# MCU.net
KiCad netlist of a schematic drawn in Altium Designer
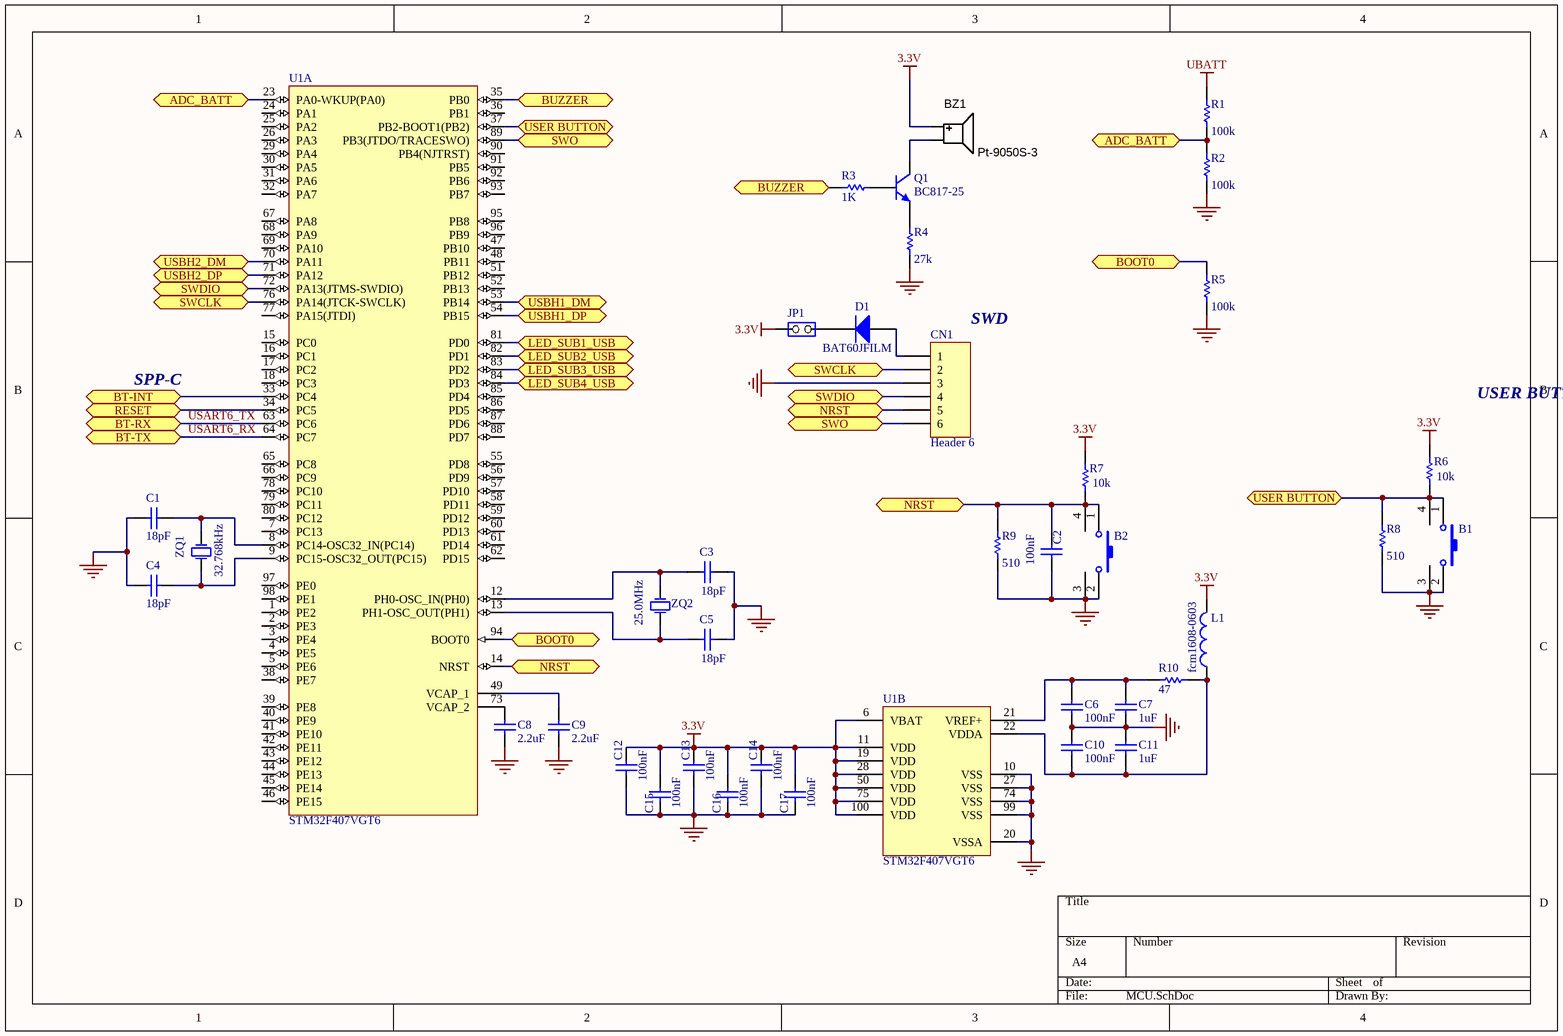
[diagram p0: MCU.SchDoc]

(export (version "E")
  (design (tool "Eeschema 10.0.6"))
  (components
    (comp (ref "B1")
      (value "SW-PB")
      (footprint "SPST-2")
      (description "Switch")
      (fields (field (name "PUBLISHER") "Altium Limited"))
      (libsource (lib "Miscellaneous Devices") (part "SW-PB"))
    )
    (comp (ref "B2")
      (value "SW-PB")
      (footprint "SPST-2")
      (description "Switch")
      (fields (field (name "PUBLISHER") "Altium Limited"))
      (libsource (lib "Miscellaneous Devices") (part "SW-PB"))
    )
    (comp (ref "BZ1")
      (value "Pt-9050S-3")
      (footprint "BUZZER_12.0X8.5MM")
      (description "Speaker, Magnetic Transducer")
      (libsource (lib "PBL - Electromechanical") (part "BZ_12x8.5x6.5_2kHz"))
    )
    (comp (ref "C1")
      (value "18pF")
      (footprint "RAD-0.3")
      (description "Capacitor")
      (fields (field (name "Comment") "Cap") (field (name "PUBLISHER") "Altium Limited"))
      (libsource (lib "Miscellaneous Devices") (part "Cap"))
    )
    (comp (ref "C2")
      (value "100nF")
      (footprint "RAD-0.3")
      (description "Capacitor")
      (fields (field (name "Comment") "Cap") (field (name "PUBLISHER") "Altium Limited"))
      (libsource (lib "Miscellaneous Devices") (part "Cap"))
    )
    (comp (ref "C3")
      (value "18pF")
      (footprint "RAD-0.3")
      (description "Capacitor")
      (fields (field (name "Comment") "Cap") (field (name "PUBLISHER") "Altium Limited"))
      (libsource (lib "Miscellaneous Devices") (part "Cap"))
    )
    (comp (ref "C4")
      (value "18pF")
      (footprint "RAD-0.3")
      (description "Capacitor")
      (fields (field (name "Comment") "Cap") (field (name "PUBLISHER") "Altium Limited"))
      (libsource (lib "Miscellaneous Devices") (part "Cap"))
    )
    (comp (ref "C5")
      (value "18pF")
      (footprint "RAD-0.3")
      (description "Capacitor")
      (fields (field (name "Comment") "Cap") (field (name "PUBLISHER") "Altium Limited"))
      (libsource (lib "Miscellaneous Devices") (part "Cap"))
    )
    (comp (ref "C6")
      (value "100nF")
      (footprint "RAD-0.3")
      (description "Capacitor")
      (fields (field (name "Comment") "Cap") (field (name "PUBLISHER") "Altium Limited"))
      (libsource (lib "Miscellaneous Devices") (part "Cap"))
    )
    (comp (ref "C7")
      (value "1uF")
      (footprint "RAD-0.3")
      (description "Capacitor")
      (fields (field (name "Comment") "Cap") (field (name "PUBLISHER") "Altium Limited"))
      (libsource (lib "Miscellaneous Devices") (part "Cap"))
    )
    (comp (ref "C8")
      (value "2.2uF")
      (footprint "RAD-0.3")
      (description "Capacitor")
      (fields (field (name "Comment") "Cap") (field (name "PUBLISHER") "Altium Limited"))
      (libsource (lib "Miscellaneous Devices") (part "Cap"))
    )
    (comp (ref "C9")
      (value "2.2uF")
      (footprint "RAD-0.3")
      (description "Capacitor")
      (fields (field (name "Comment") "Cap") (field (name "PUBLISHER") "Altium Limited"))
      (libsource (lib "Miscellaneous Devices") (part "Cap"))
    )
    (comp (ref "C10")
      (value "100nF")
      (footprint "RAD-0.3")
      (description "Capacitor")
      (fields (field (name "Comment") "Cap") (field (name "PUBLISHER") "Altium Limited"))
      (libsource (lib "Miscellaneous Devices") (part "Cap"))
    )
    (comp (ref "C11")
      (value "1uF")
      (footprint "RAD-0.3")
      (description "Capacitor")
      (fields (field (name "Comment") "Cap") (field (name "PUBLISHER") "Altium Limited"))
      (libsource (lib "Miscellaneous Devices") (part "Cap"))
    )
    (comp (ref "C12")
      (value "100nF")
      (footprint "RAD-0.3")
      (description "Capacitor")
      (fields (field (name "Comment") "Cap") (field (name "PUBLISHER") "Altium Limited"))
      (libsource (lib "Miscellaneous Devices") (part "Cap"))
    )
    (comp (ref "C13")
      (value "100nF")
      (footprint "RAD-0.3")
      (description "Capacitor")
      (fields (field (name "Comment") "Cap") (field (name "PUBLISHER") "Altium Limited"))
      (libsource (lib "Miscellaneous Devices") (part "Cap"))
    )
    (comp (ref "C14")
      (value "100nF")
      (footprint "RAD-0.3")
      (description "Capacitor")
      (fields (field (name "Comment") "Cap") (field (name "PUBLISHER") "Altium Limited"))
      (libsource (lib "Miscellaneous Devices") (part "Cap"))
    )
    (comp (ref "C15")
      (value "100nF")
      (footprint "RAD-0.3")
      (description "Capacitor")
      (fields (field (name "Comment") "Cap") (field (name "PUBLISHER") "Altium Limited"))
      (libsource (lib "Miscellaneous Devices") (part "Cap"))
    )
    (comp (ref "C16")
      (value "100nF")
      (footprint "RAD-0.3")
      (description "Capacitor")
      (fields (field (name "Comment") "Cap") (field (name "PUBLISHER") "Altium Limited"))
      (libsource (lib "Miscellaneous Devices") (part "Cap"))
    )
    (comp (ref "C17")
      (value "100nF")
      (footprint "RAD-0.3")
      (description "Capacitor")
      (fields (field (name "Comment") "Cap") (field (name "PUBLISHER") "Altium Limited"))
      (libsource (lib "Miscellaneous Devices") (part "Cap"))
    )
    (comp (ref "CN1")
      (value "Header 6")
      (footprint "HDR1X6")
      (description "Header, 6-Pin")
      (fields (field (name "PUBLISHER") "Altium Limited"))
      (libsource (lib "Miscellaneous Connectors") (part "Header 6"))
    )
    (comp (ref "D1")
      (value "BAT60JFILM")
      (footprint "SOD323/A")
      (fields (field (name "PUBLISHER") "Altium Limited"))
      (libsource (lib "MB997") (part "BAT60JFILM"))
    )
    (comp (ref "JP1") (value "~") (footprint "SIP2/2.54") (libsource (lib "*") (part "JP2")))
    (comp (ref "L1")
      (value "fcm1608-0603")
      (footprint "0402-A")
      (description "Inductor")
      (fields (field (name "PUBLISHER") "Altium Limited"))
      (libsource (lib "Miscellaneous Devices") (part "Inductor"))
    )
    (comp (ref "Q1")
      (value "BC817-25")
      (footprint "TO-226-AA")
      (description "NPN Bipolar Transistor")
      (fields (field (name "PUBLISHER") "Altium Limited"))
      (libsource (lib "Miscellaneous Devices") (part "NPN"))
    )
    (comp (ref "R1")
      (value "100k")
      (footprint "AXIAL-0.3")
      (description "Resistor")
      (fields (field (name "Comment") "Res1") (field (name "PUBLISHER") "Altium Limited"))
      (libsource (lib "Miscellaneous Devices") (part "Res1"))
    )
    (comp (ref "R2")
      (value "100k")
      (footprint "AXIAL-0.3")
      (description "Resistor")
      (fields (field (name "Comment") "Res1") (field (name "PUBLISHER") "Altium Limited"))
      (libsource (lib "Miscellaneous Devices") (part "Res1"))
    )
    (comp (ref "R3")
      (value "1K")
      (footprint "AXIAL-0.3")
      (description "Resistor")
      (fields (field (name "Comment") "Res1") (field (name "PUBLISHER") "Altium Limited"))
      (libsource (lib "Miscellaneous Devices") (part "Res1"))
    )
    (comp (ref "R4")
      (value "27k")
      (footprint "AXIAL-0.3")
      (description "Resistor")
      (fields (field (name "Comment") "Res1") (field (name "PUBLISHER") "Altium Limited"))
      (libsource (lib "Miscellaneous Devices") (part "Res1"))
    )
    (comp (ref "R5")
      (value "100k")
      (footprint "AXIAL-0.3")
      (description "Resistor")
      (fields (field (name "Comment") "Res1") (field (name "PUBLISHER") "Altium Limited"))
      (libsource (lib "Miscellaneous Devices") (part "Res1"))
    )
    (comp (ref "R6")
      (value "10k")
      (footprint "AXIAL-0.3")
      (description "Resistor")
      (fields (field (name "Comment") "Res1") (field (name "PUBLISHER") "Altium Limited"))
      (libsource (lib "Miscellaneous Devices") (part "Res1"))
    )
    (comp (ref "R7")
      (value "10k")
      (footprint "AXIAL-0.3")
      (description "Resistor")
      (fields (field (name "Comment") "Res1") (field (name "PUBLISHER") "Altium Limited"))
      (libsource (lib "Miscellaneous Devices") (part "Res1"))
    )
    (comp (ref "R8")
      (value "510")
      (footprint "AXIAL-0.3")
      (description "Resistor")
      (fields (field (name "Comment") "Res1") (field (name "PUBLISHER") "Altium Limited"))
      (libsource (lib "Miscellaneous Devices") (part "Res1"))
    )
    (comp (ref "R9")
      (value "510")
      (footprint "AXIAL-0.3")
      (description "Resistor")
      (fields (field (name "Comment") "Res1") (field (name "PUBLISHER") "Altium Limited"))
      (libsource (lib "Miscellaneous Devices") (part "Res1"))
    )
    (comp (ref "R10")
      (value "47")
      (footprint "AXIAL-0.3")
      (description "Resistor")
      (fields (field (name "Comment") "Res1") (field (name "PUBLISHER") "Altium Limited"))
      (libsource (lib "Miscellaneous Devices") (part "Res1"))
    )
    (comp (ref "U1")
      (value "STM32F407VGT6")
      (footprint "STM-LQFP100_N")
      (fields (field (name "MANUFACTURER") "STMicroelectronics"))
      (libsource (lib "") (part "STM32F407VGT6_1"))
    )
    (comp (ref "ZQ1")
      (value "32.768kHz")
      (footprint "R38")
      (description "Crystal Oscillator")
      (fields (field (name "Comment") "XTAL") (field (name "PUBLISHER") "Altium Limited"))
      (libsource (lib "Miscellaneous Devices") (part "XTAL"))
    )
    (comp (ref "ZQ2")
      (value "25.0MHz")
      (footprint "R38")
      (description "Crystal Oscillator")
      (fields (field (name "Comment") "XTAL") (field (name "PUBLISHER") "Altium Limited"))
      (libsource (lib "Miscellaneous Devices") (part "XTAL"))
    )
  )
  (nets
    (net (code "1") (name "/ADC_BATT") (class "Default")
      (node (ref "R1") (pin "1") (pinfunction "1_1") (pintype "passive"))
      (node (ref "R2") (pin "2") (pinfunction "2_2") (pintype "passive"))
      (node (ref "U1") (pin "23") (pinfunction "PA0-WKUP(PA0)_23") (pintype "bidirectional"))
    )
    (net (code "2") (name "/BOOT0") (class "Default")
      (node (ref "R5") (pin "2") (pinfunction "2_2") (pintype "passive"))
      (node (ref "U1") (pin "94") (pinfunction "BOOT0_94") (pintype "input"))
    )
    (net (code "3") (name "/BT-INT") (class "Default")
      (node (ref "U1") (pin "33") (pinfunction "PC4_33") (pintype "bidirectional"))
    )
    (net (code "4") (name "/BUZZER") (class "Default")
      (node (ref "R3") (pin "2") (pinfunction "2_2") (pintype "passive"))
      (node (ref "U1") (pin "35") (pinfunction "PB0_35") (pintype "bidirectional"))
    )
    (net (code "5") (name "/LED_SUB1_USB") (class "Default")
      (node (ref "U1") (pin "81") (pinfunction "PD0_81") (pintype "bidirectional"))
    )
    (net (code "6") (name "/LED_SUB2_USB") (class "Default")
      (node (ref "U1") (pin "82") (pinfunction "PD1_82") (pintype "bidirectional"))
    )
    (net (code "7") (name "/LED_SUB3_USB") (class "Default")
      (node (ref "U1") (pin "83") (pinfunction "PD2_83") (pintype "bidirectional"))
    )
    (net (code "8") (name "/LED_SUB4_USB") (class "Default")
      (node (ref "U1") (pin "84") (pinfunction "PD3_84") (pintype "bidirectional"))
    )
    (net (code "9") (name "/NRST") (class "Default")
      (node (ref "B2") (pin "1") (pinfunction "1_1") (pintype "passive"))
      (node (ref "B2") (pin "4") (pinfunction "4_4") (pintype "passive"))
      (node (ref "C2") (pin "2") (pinfunction "2_2") (pintype "passive"))
      (node (ref "CN1") (pin "5") (pinfunction "5_5") (pintype "passive"))
      (node (ref "R7") (pin "1") (pinfunction "1_1") (pintype "passive"))
      (node (ref "R9") (pin "2") (pinfunction "2_2") (pintype "passive"))
      (node (ref "U1") (pin "14") (pinfunction "NRST_14") (pintype "bidirectional"))
    )
    (net (code "10") (name "/RESET") (class "Default")
      (node (ref "U1") (pin "34") (pinfunction "PC5_34") (pintype "bidirectional"))
    )
    (net (code "11") (name "/SWCLK") (class "Default")
      (node (ref "CN1") (pin "2") (pinfunction "2_2") (pintype "passive"))
      (node (ref "U1") (pin "76") (pinfunction "PA14(JTCK-SWCLK)_76") (pintype "bidirectional"))
    )
    (net (code "12") (name "/SWDIO") (class "Default")
      (node (ref "CN1") (pin "4") (pinfunction "4_4") (pintype "passive"))
      (node (ref "U1") (pin "72") (pinfunction "PA13(JTMS-SWDIO)_72") (pintype "bidirectional"))
    )
    (net (code "13") (name "/SWO") (class "Default")
      (node (ref "CN1") (pin "6") (pinfunction "6_6") (pintype "passive"))
      (node (ref "U1") (pin "89") (pinfunction "PB3(JTDO/TRACESWO)_89") (pintype "bidirectional"))
    )
    (net (code "14") (name "/USART6_RX") (class "Default")
      (node (ref "U1") (pin "64") (pinfunction "PC7_64") (pintype "bidirectional"))
    )
    (net (code "15") (name "/USART6_TX") (class "Default")
      (node (ref "U1") (pin "63") (pinfunction "PC6_63") (pintype "bidirectional"))
    )
    (net (code "16") (name "/USBH1_DM") (class "Default")
      (node (ref "U1") (pin "53") (pinfunction "PB14_53") (pintype "bidirectional"))
    )
    (net (code "17") (name "/USBH1_DP") (class "Default")
      (node (ref "U1") (pin "54") (pinfunction "PB15_54") (pintype "bidirectional"))
    )
    (net (code "18") (name "/USBH2_DM") (class "Default")
      (node (ref "U1") (pin "70") (pinfunction "PA11_70") (pintype "bidirectional"))
    )
    (net (code "19") (name "/USBH2_DP") (class "Default")
      (node (ref "U1") (pin "71") (pinfunction "PA12_71") (pintype "bidirectional"))
    )
    (net (code "20") (name "/USER BUTTON") (class "Default")
      (node (ref "B1") (pin "1") (pinfunction "1_1") (pintype "passive"))
      (node (ref "B1") (pin "4") (pinfunction "4_4") (pintype "passive"))
      (node (ref "R6") (pin "1") (pinfunction "1_1") (pintype "passive"))
      (node (ref "R8") (pin "2") (pinfunction "2_2") (pintype "passive"))
      (node (ref "U1") (pin "37") (pinfunction "PB2-BOOT1(PB2)_37") (pintype "bidirectional"))
    )
    (net (code "21") (name "3.3V") (class "Default")
      (node (ref "BZ1") (pin "1") (pinfunction "Positive_1") (pintype "passive"))
      (node (ref "C12") (pin "1") (pinfunction "1_1") (pintype "passive"))
      (node (ref "C13") (pin "1") (pinfunction "1_1") (pintype "passive"))
      (node (ref "C14") (pin "1") (pinfunction "1_1") (pintype "passive"))
      (node (ref "C15") (pin "1") (pinfunction "1_1") (pintype "passive"))
      (node (ref "C16") (pin "1") (pinfunction "1_1") (pintype "passive"))
      (node (ref "C17") (pin "1") (pinfunction "1_1") (pintype "passive"))
      (node (ref "JP1") (pin "2") (pinfunction "NO_2") (pintype "passive"))
      (node (ref "L1") (pin "2") (pinfunction "2_2") (pintype "passive"))
      (node (ref "R6") (pin "2") (pinfunction "2_2") (pintype "passive"))
      (node (ref "R7") (pin "2") (pinfunction "2_2") (pintype "passive"))
      (node (ref "U1") (pin "100") (pinfunction "VDD_100") (pintype "power_in"))
      (node (ref "U1") (pin "11") (pinfunction "VDD_11") (pintype "power_in"))
      (node (ref "U1") (pin "19") (pinfunction "VDD_19") (pintype "power_in"))
      (node (ref "U1") (pin "28") (pinfunction "VDD_28") (pintype "power_in"))
      (node (ref "U1") (pin "50") (pinfunction "VDD_50") (pintype "power_in"))
      (node (ref "U1") (pin "6") (pinfunction "VBAT_6") (pintype "power_in"))
      (node (ref "U1") (pin "75") (pinfunction "VDD_75") (pintype "power_in"))
    )
    (net (code "22") (name "GND") (class "Default")
      (node (ref "B1") (pin "2") (pinfunction "2_2") (pintype "passive"))
      (node (ref "B1") (pin "3") (pinfunction "3_3") (pintype "passive"))
      (node (ref "B2") (pin "2") (pinfunction "2_2") (pintype "passive"))
      (node (ref "B2") (pin "3") (pinfunction "3_3") (pintype "passive"))
      (node (ref "C1") (pin "2") (pinfunction "2_2") (pintype "passive"))
      (node (ref "C10") (pin "2") (pinfunction "2_2") (pintype "passive"))
      (node (ref "C11") (pin "2") (pinfunction "2_2") (pintype "passive"))
      (node (ref "C12") (pin "2") (pinfunction "2_2") (pintype "passive"))
      (node (ref "C13") (pin "2") (pinfunction "2_2") (pintype "passive"))
      (node (ref "C14") (pin "2") (pinfunction "2_2") (pintype "passive"))
      (node (ref "C15") (pin "2") (pinfunction "2_2") (pintype "passive"))
      (node (ref "C16") (pin "2") (pinfunction "2_2") (pintype "passive"))
      (node (ref "C17") (pin "2") (pinfunction "2_2") (pintype "passive"))
      (node (ref "C2") (pin "1") (pinfunction "1_1") (pintype "passive"))
      (node (ref "C3") (pin "2") (pinfunction "2_2") (pintype "passive"))
      (node (ref "C4") (pin "2") (pinfunction "2_2") (pintype "passive"))
      (node (ref "C5") (pin "2") (pinfunction "2_2") (pintype "passive"))
      (node (ref "C6") (pin "1") (pinfunction "1_1") (pintype "passive"))
      (node (ref "C7") (pin "1") (pinfunction "1_1") (pintype "passive"))
      (node (ref "C8") (pin "2") (pinfunction "2_2") (pintype "passive"))
      (node (ref "C9") (pin "2") (pinfunction "2_2") (pintype "passive"))
      (node (ref "CN1") (pin "3") (pinfunction "3_3") (pintype "passive"))
      (node (ref "R2") (pin "1") (pinfunction "1_1") (pintype "passive"))
      (node (ref "R4") (pin "1") (pinfunction "1_1") (pintype "passive"))
      (node (ref "R5") (pin "1") (pinfunction "1_1") (pintype "passive"))
      (node (ref "R8") (pin "1") (pinfunction "1_1") (pintype "passive"))
      (node (ref "R9") (pin "1") (pinfunction "1_1") (pintype "passive"))
      (node (ref "U1") (pin "10") (pinfunction "VSS_10") (pintype "power_in"))
      (node (ref "U1") (pin "20") (pinfunction "VSSA_20") (pintype "power_in"))
      (node (ref "U1") (pin "27") (pinfunction "VSS_27") (pintype "power_in"))
      (node (ref "U1") (pin "74") (pinfunction "VSS_74") (pintype "power_in"))
      (node (ref "U1") (pin "99") (pinfunction "VSS_99") (pintype "power_in"))
    )
    (net (code "23") (name "Net-(BZ1-Negative)") (class "Default")
      (node (ref "BZ1") (pin "2") (pinfunction "Negative_2") (pintype "passive"))
      (node (ref "Q1") (pin "1") (pinfunction "C_1") (pintype "passive"))
    )
    (net (code "24") (name "Net-(D1-A)") (class "Default")
      (node (ref "CN1") (pin "1") (pinfunction "1_1") (pintype "passive"))
      (node (ref "D1") (pin "1") (pinfunction "A_1") (pintype "passive"))
    )
    (net (code "25") (name "Net-(D1-K)") (class "Default")
      (node (ref "D1") (pin "2") (pinfunction "K_2") (pintype "passive"))
      (node (ref "JP1") (pin "1") (pinfunction "COMMON_1") (pintype "passive"))
    )
    (net (code "26") (name "Net-(Q1-B)") (class "Default")
      (node (ref "Q1") (pin "2") (pinfunction "B_2") (pintype "passive"))
      (node (ref "R3") (pin "1") (pinfunction "1_1") (pintype "passive"))
    )
    (net (code "27") (name "Net-(Q1-E)") (class "Default")
      (node (ref "Q1") (pin "3") (pinfunction "E_3") (pintype "passive"))
      (node (ref "R4") (pin "2") (pinfunction "2_2") (pintype "passive"))
    )
    (net (code "28") (name "Net-(U1A-PC14-OSC32_IN(PC14))") (class "Default")
      (node (ref "C1") (pin "1") (pinfunction "1_1") (pintype "passive"))
      (node (ref "U1") (pin "8") (pinfunction "PC14-OSC32_IN(PC14)_8") (pintype "bidirectional"))
      (node (ref "ZQ1") (pin "2") (pinfunction "OSC2_2") (pintype "passive"))
    )
    (net (code "29") (name "Net-(U1A-PC15-OSC32_OUT(PC15))") (class "Default")
      (node (ref "C4") (pin "1") (pinfunction "1_1") (pintype "passive"))
      (node (ref "U1") (pin "9") (pinfunction "PC15-OSC32_OUT(PC15)_9") (pintype "bidirectional"))
      (node (ref "ZQ1") (pin "1") (pinfunction "OSC1_1") (pintype "passive"))
    )
    (net (code "30") (name "Net-(U1A-PH0-OSC_IN(PH0))") (class "Default")
      (node (ref "C3") (pin "1") (pinfunction "1_1") (pintype "passive"))
      (node (ref "U1") (pin "12") (pinfunction "PH0-OSC_IN(PH0)_12") (pintype "bidirectional"))
      (node (ref "ZQ2") (pin "1") (pinfunction "OSC1_1") (pintype "passive"))
    )
    (net (code "31") (name "Net-(U1A-PH1-OSC_OUT(PH1))") (class "Default")
      (node (ref "C5") (pin "1") (pinfunction "1_1") (pintype "passive"))
      (node (ref "U1") (pin "13") (pinfunction "PH1-OSC_OUT(PH1)_13") (pintype "bidirectional"))
      (node (ref "ZQ2") (pin "2") (pinfunction "OSC2_2") (pintype "passive"))
    )
    (net (code "32") (name "Net-(U1A-VCAP_1)") (class "Default")
      (node (ref "C9") (pin "1") (pinfunction "1_1") (pintype "passive"))
      (node (ref "U1") (pin "49") (pinfunction "VCAP_1_49") (pintype "power_in"))
    )
    (net (code "33") (name "Net-(U1A-VCAP_2)") (class "Default")
      (node (ref "C8") (pin "1") (pinfunction "1_1") (pintype "passive"))
      (node (ref "U1") (pin "73") (pinfunction "VCAP_2_73") (pintype "power_in"))
    )
    (net (code "34") (name "Net-(U1B-VDDA)") (class "Default")
      (node (ref "C10") (pin "1") (pinfunction "1_1") (pintype "passive"))
      (node (ref "C11") (pin "1") (pinfunction "1_1") (pintype "passive"))
      (node (ref "L1") (pin "1") (pinfunction "1_1") (pintype "passive"))
      (node (ref "R10") (pin "1") (pinfunction "1_1") (pintype "passive"))
      (node (ref "U1") (pin "22") (pinfunction "VDDA_22") (pintype "power_in"))
    )
    (net (code "35") (name "Net-(U1B-VREF+)") (class "Default")
      (node (ref "C6") (pin "2") (pinfunction "2_2") (pintype "passive"))
      (node (ref "C7") (pin "2") (pinfunction "2_2") (pintype "passive"))
      (node (ref "R10") (pin "2") (pinfunction "2_2") (pintype "passive"))
      (node (ref "U1") (pin "21") (pinfunction "VREF+_21") (pintype "power_in"))
    )
    (net (code "36") (name "UBATT") (class "Default")
      (node (ref "R1") (pin "2") (pinfunction "2_2") (pintype "passive"))
    )
    (net (code "37") (name "unconnected-(U1A-PA1-Pad24)") (class "Default")
      (node (ref "U1") (pin "24") (pinfunction "PA1_24") (pintype "bidirectional"))
    )
    (net (code "38") (name "unconnected-(U1A-PA2-Pad25)") (class "Default")
      (node (ref "U1") (pin "25") (pinfunction "PA2_25") (pintype "bidirectional"))
    )
    (net (code "39") (name "unconnected-(U1A-PA3-Pad26)") (class "Default")
      (node (ref "U1") (pin "26") (pinfunction "PA3_26") (pintype "bidirectional"))
    )
    (net (code "40") (name "unconnected-(U1A-PA4-Pad29)") (class "Default")
      (node (ref "U1") (pin "29") (pinfunction "PA4_29") (pintype "bidirectional"))
    )
    (net (code "41") (name "unconnected-(U1A-PA5-Pad30)") (class "Default")
      (node (ref "U1") (pin "30") (pinfunction "PA5_30") (pintype "bidirectional"))
    )
    (net (code "42") (name "unconnected-(U1A-PA6-Pad31)") (class "Default")
      (node (ref "U1") (pin "31") (pinfunction "PA6_31") (pintype "bidirectional"))
    )
    (net (code "43") (name "unconnected-(U1A-PA7-Pad32)") (class "Default")
      (node (ref "U1") (pin "32") (pinfunction "PA7_32") (pintype "bidirectional"))
    )
    (net (code "44") (name "unconnected-(U1A-PA8-Pad67)") (class "Default")
      (node (ref "U1") (pin "67") (pinfunction "PA8_67") (pintype "bidirectional"))
    )
    (net (code "45") (name "unconnected-(U1A-PA9-Pad68)") (class "Default")
      (node (ref "U1") (pin "68") (pinfunction "PA9_68") (pintype "bidirectional"))
    )
    (net (code "46") (name "unconnected-(U1A-PA10-Pad69)") (class "Default")
      (node (ref "U1") (pin "69") (pinfunction "PA10_69") (pintype "bidirectional"))
    )
    (net (code "47") (name "unconnected-(U1A-PA15(JTDI)-Pad77)") (class "Default")
      (node (ref "U1") (pin "77") (pinfunction "PA15(JTDI)_77") (pintype "bidirectional"))
    )
    (net (code "48") (name "unconnected-(U1A-PB1-Pad36)") (class "Default")
      (node (ref "U1") (pin "36") (pinfunction "PB1_36") (pintype "bidirectional"))
    )
    (net (code "49") (name "unconnected-(U1A-PB4(NJTRST)-Pad90)") (class "Default")
      (node (ref "U1") (pin "90") (pinfunction "PB4(NJTRST)_90") (pintype "bidirectional"))
    )
    (net (code "50") (name "unconnected-(U1A-PB5-Pad91)") (class "Default")
      (node (ref "U1") (pin "91") (pinfunction "PB5_91") (pintype "bidirectional"))
    )
    (net (code "51") (name "unconnected-(U1A-PB6-Pad92)") (class "Default")
      (node (ref "U1") (pin "92") (pinfunction "PB6_92") (pintype "bidirectional"))
    )
    (net (code "52") (name "unconnected-(U1A-PB7-Pad93)") (class "Default")
      (node (ref "U1") (pin "93") (pinfunction "PB7_93") (pintype "bidirectional"))
    )
    (net (code "53") (name "unconnected-(U1A-PB8-Pad95)") (class "Default")
      (node (ref "U1") (pin "95") (pinfunction "PB8_95") (pintype "bidirectional"))
    )
    (net (code "54") (name "unconnected-(U1A-PB9-Pad96)") (class "Default")
      (node (ref "U1") (pin "96") (pinfunction "PB9_96") (pintype "bidirectional"))
    )
    (net (code "55") (name "unconnected-(U1A-PB10-Pad47)") (class "Default")
      (node (ref "U1") (pin "47") (pinfunction "PB10_47") (pintype "bidirectional"))
    )
    (net (code "56") (name "unconnected-(U1A-PB11-Pad48)") (class "Default")
      (node (ref "U1") (pin "48") (pinfunction "PB11_48") (pintype "bidirectional"))
    )
    (net (code "57") (name "unconnected-(U1A-PB12-Pad51)") (class "Default")
      (node (ref "U1") (pin "51") (pinfunction "PB12_51") (pintype "bidirectional"))
    )
    (net (code "58") (name "unconnected-(U1A-PB13-Pad52)") (class "Default")
      (node (ref "U1") (pin "52") (pinfunction "PB13_52") (pintype "bidirectional"))
    )
    (net (code "59") (name "unconnected-(U1A-PC0-Pad15)") (class "Default")
      (node (ref "U1") (pin "15") (pinfunction "PC0_15") (pintype "bidirectional"))
    )
    (net (code "60") (name "unconnected-(U1A-PC1-Pad16)") (class "Default")
      (node (ref "U1") (pin "16") (pinfunction "PC1_16") (pintype "bidirectional"))
    )
    (net (code "61") (name "unconnected-(U1A-PC2-Pad17)") (class "Default")
      (node (ref "U1") (pin "17") (pinfunction "PC2_17") (pintype "bidirectional"))
    )
    (net (code "62") (name "unconnected-(U1A-PC3-Pad18)") (class "Default")
      (node (ref "U1") (pin "18") (pinfunction "PC3_18") (pintype "bidirectional"))
    )
    (net (code "63") (name "unconnected-(U1A-PC8-Pad65)") (class "Default")
      (node (ref "U1") (pin "65") (pinfunction "PC8_65") (pintype "bidirectional"))
    )
    (net (code "64") (name "unconnected-(U1A-PC9-Pad66)") (class "Default")
      (node (ref "U1") (pin "66") (pinfunction "PC9_66") (pintype "bidirectional"))
    )
    (net (code "65") (name "unconnected-(U1A-PC10-Pad78)") (class "Default")
      (node (ref "U1") (pin "78") (pinfunction "PC10_78") (pintype "bidirectional"))
    )
    (net (code "66") (name "unconnected-(U1A-PC11-Pad79)") (class "Default")
      (node (ref "U1") (pin "79") (pinfunction "PC11_79") (pintype "bidirectional"))
    )
    (net (code "67") (name "unconnected-(U1A-PC12-Pad80)") (class "Default")
      (node (ref "U1") (pin "80") (pinfunction "PC12_80") (pintype "bidirectional"))
    )
    (net (code "68") (name "unconnected-(U1A-PC13-Pad7)") (class "Default")
      (node (ref "U1") (pin "7") (pinfunction "PC13_7") (pintype "bidirectional"))
    )
    (net (code "69") (name "unconnected-(U1A-PD4-Pad85)") (class "Default")
      (node (ref "U1") (pin "85") (pinfunction "PD4_85") (pintype "bidirectional"))
    )
    (net (code "70") (name "unconnected-(U1A-PD5-Pad86)") (class "Default")
      (node (ref "U1") (pin "86") (pinfunction "PD5_86") (pintype "bidirectional"))
    )
    (net (code "71") (name "unconnected-(U1A-PD6-Pad87)") (class "Default")
      (node (ref "U1") (pin "87") (pinfunction "PD6_87") (pintype "bidirectional"))
    )
    (net (code "72") (name "unconnected-(U1A-PD7-Pad88)") (class "Default")
      (node (ref "U1") (pin "88") (pinfunction "PD7_88") (pintype "bidirectional"))
    )
    (net (code "73") (name "unconnected-(U1A-PD8-Pad55)") (class "Default")
      (node (ref "U1") (pin "55") (pinfunction "PD8_55") (pintype "bidirectional"))
    )
    (net (code "74") (name "unconnected-(U1A-PD9-Pad56)") (class "Default")
      (node (ref "U1") (pin "56") (pinfunction "PD9_56") (pintype "bidirectional"))
    )
    (net (code "75") (name "unconnected-(U1A-PD10-Pad57)") (class "Default")
      (node (ref "U1") (pin "57") (pinfunction "PD10_57") (pintype "bidirectional"))
    )
    (net (code "76") (name "unconnected-(U1A-PD11-Pad58)") (class "Default")
      (node (ref "U1") (pin "58") (pinfunction "PD11_58") (pintype "bidirectional"))
    )
    (net (code "77") (name "unconnected-(U1A-PD12-Pad59)") (class "Default")
      (node (ref "U1") (pin "59") (pinfunction "PD12_59") (pintype "bidirectional"))
    )
    (net (code "78") (name "unconnected-(U1A-PD13-Pad60)") (class "Default")
      (node (ref "U1") (pin "60") (pinfunction "PD13_60") (pintype "bidirectional"))
    )
    (net (code "79") (name "unconnected-(U1A-PD14-Pad61)") (class "Default")
      (node (ref "U1") (pin "61") (pinfunction "PD14_61") (pintype "bidirectional"))
    )
    (net (code "80") (name "unconnected-(U1A-PD15-Pad62)") (class "Default")
      (node (ref "U1") (pin "62") (pinfunction "PD15_62") (pintype "bidirectional"))
    )
    (net (code "81") (name "unconnected-(U1A-PE0-Pad97)") (class "Default")
      (node (ref "U1") (pin "97") (pinfunction "PE0_97") (pintype "bidirectional"))
    )
    (net (code "82") (name "unconnected-(U1A-PE1-Pad98)") (class "Default")
      (node (ref "U1") (pin "98") (pinfunction "PE1_98") (pintype "bidirectional"))
    )
    (net (code "83") (name "unconnected-(U1A-PE2-Pad1)") (class "Default")
      (node (ref "U1") (pin "1") (pinfunction "PE2_1") (pintype "bidirectional"))
    )
    (net (code "84") (name "unconnected-(U1A-PE3-Pad2)") (class "Default")
      (node (ref "U1") (pin "2") (pinfunction "PE3_2") (pintype "bidirectional"))
    )
    (net (code "85") (name "unconnected-(U1A-PE4-Pad3)") (class "Default")
      (node (ref "U1") (pin "3") (pinfunction "PE4_3") (pintype "bidirectional"))
    )
    (net (code "86") (name "unconnected-(U1A-PE5-Pad4)") (class "Default")
      (node (ref "U1") (pin "4") (pinfunction "PE5_4") (pintype "bidirectional"))
    )
    (net (code "87") (name "unconnected-(U1A-PE6-Pad5)") (class "Default")
      (node (ref "U1") (pin "5") (pinfunction "PE6_5") (pintype "bidirectional"))
    )
    (net (code "88") (name "unconnected-(U1A-PE7-Pad38)") (class "Default")
      (node (ref "U1") (pin "38") (pinfunction "PE7_38") (pintype "bidirectional"))
    )
    (net (code "89") (name "unconnected-(U1A-PE8-Pad39)") (class "Default")
      (node (ref "U1") (pin "39") (pinfunction "PE8_39") (pintype "bidirectional"))
    )
    (net (code "90") (name "unconnected-(U1A-PE9-Pad40)") (class "Default")
      (node (ref "U1") (pin "40") (pinfunction "PE9_40") (pintype "bidirectional"))
    )
    (net (code "91") (name "unconnected-(U1A-PE10-Pad41)") (class "Default")
      (node (ref "U1") (pin "41") (pinfunction "PE10_41") (pintype "bidirectional"))
    )
    (net (code "92") (name "unconnected-(U1A-PE11-Pad42)") (class "Default")
      (node (ref "U1") (pin "42") (pinfunction "PE11_42") (pintype "bidirectional"))
    )
    (net (code "93") (name "unconnected-(U1A-PE12-Pad43)") (class "Default")
      (node (ref "U1") (pin "43") (pinfunction "PE12_43") (pintype "bidirectional"))
    )
    (net (code "94") (name "unconnected-(U1A-PE13-Pad44)") (class "Default")
      (node (ref "U1") (pin "44") (pinfunction "PE13_44") (pintype "bidirectional"))
    )
    (net (code "95") (name "unconnected-(U1A-PE14-Pad45)") (class "Default")
      (node (ref "U1") (pin "45") (pinfunction "PE14_45") (pintype "bidirectional"))
    )
    (net (code "96") (name "unconnected-(U1A-PE15-Pad46)") (class "Default")
      (node (ref "U1") (pin "46") (pinfunction "PE15_46") (pintype "bidirectional"))
    )
  )
)
